# design.net
KiCad netlist of a schematic drawn in EasyEDA Pro
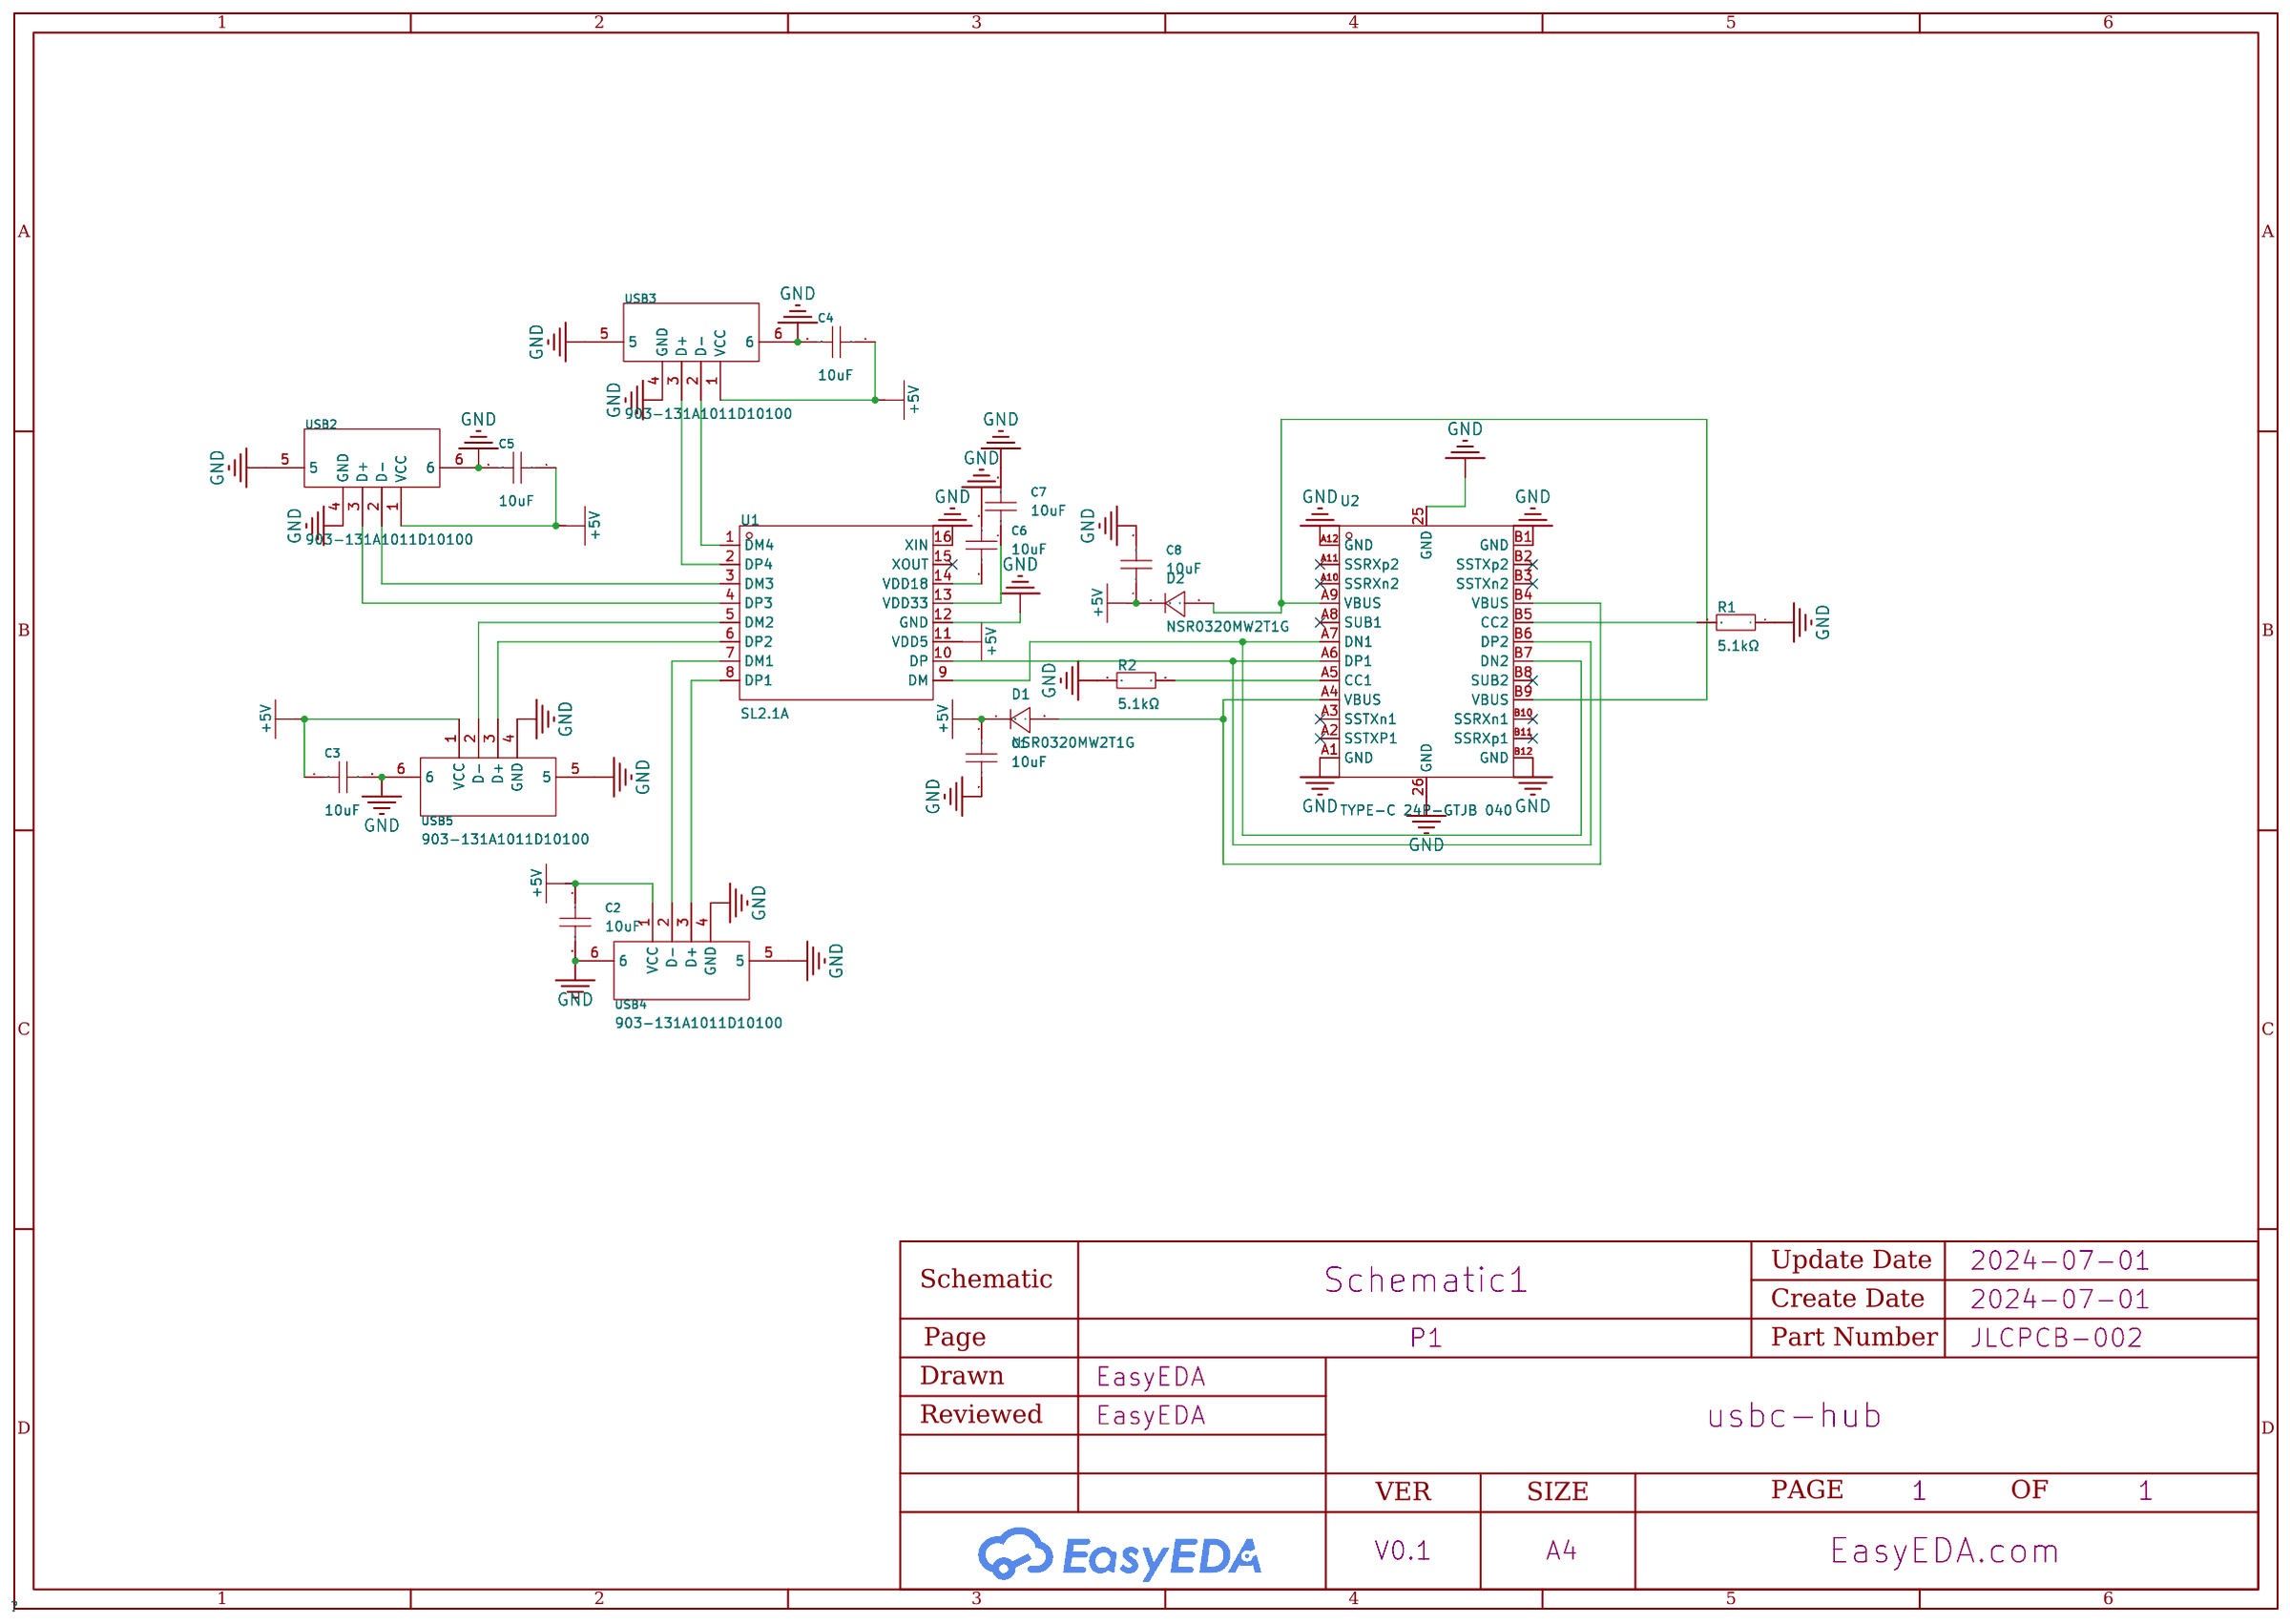
[diagram p0: schematic sheet]

(export (version "E")
  (design (tool "Eeschema 10.0.6"))
  (components
    (comp (ref "C1")
      (value "10uF")
      (footprint "easyedapro:C0603")
      (fields
        (field (name "Manufacturer Part") "CL10A106KP8NNNC")
        (field (name "Manufacturer") "SAMSUNG(三星)")
      )
      (libsource (lib "easyedapro") (part "CL10A106KP8NNNC"))
    )
    (comp (ref "C2")
      (value "10uF")
      (footprint "easyedapro:C0603")
      (fields
        (field (name "Manufacturer Part") "CL10A106KP8NNNC")
        (field (name "Manufacturer") "SAMSUNG(三星)")
      )
      (libsource (lib "easyedapro") (part "CL10A106KP8NNNC"))
    )
    (comp (ref "C3")
      (value "10uF")
      (footprint "easyedapro:C0603")
      (fields
        (field (name "Manufacturer Part") "CL10A106KP8NNNC")
        (field (name "Manufacturer") "SAMSUNG(三星)")
      )
      (libsource (lib "easyedapro") (part "CL10A106KP8NNNC"))
    )
    (comp (ref "C4")
      (value "10uF")
      (footprint "easyedapro:C0603")
      (fields
        (field (name "Manufacturer Part") "CL10A106KP8NNNC")
        (field (name "Manufacturer") "SAMSUNG(三星)")
      )
      (libsource (lib "easyedapro") (part "CL10A106KP8NNNC"))
    )
    (comp (ref "C5")
      (value "10uF")
      (footprint "easyedapro:C0603")
      (fields
        (field (name "Manufacturer Part") "CL10A106KP8NNNC")
        (field (name "Manufacturer") "SAMSUNG(三星)")
      )
      (libsource (lib "easyedapro") (part "CL10A106KP8NNNC"))
    )
    (comp (ref "C6")
      (value "10uF")
      (footprint "easyedapro:C0603")
      (fields
        (field (name "Manufacturer Part") "CL10A106KP8NNNC")
        (field (name "Manufacturer") "SAMSUNG(三星)")
      )
      (libsource (lib "easyedapro") (part "CL10A106KP8NNNC"))
    )
    (comp (ref "C7")
      (value "10uF")
      (footprint "easyedapro:C0603")
      (fields
        (field (name "Manufacturer Part") "CL10A106KP8NNNC")
        (field (name "Manufacturer") "SAMSUNG(三星)")
      )
      (libsource (lib "easyedapro") (part "CL10A106KP8NNNC"))
    )
    (comp (ref "C8")
      (value "10uF")
      (footprint "easyedapro:C0603")
      (fields
        (field (name "Manufacturer Part") "CL10A106KP8NNNC")
        (field (name "Manufacturer") "SAMSUNG(三星)")
      )
      (libsource (lib "easyedapro") (part "CL10A106KP8NNNC"))
    )
    (comp (ref "D1")
      (value "NSR0320MW2T1G")
      (footprint "easyedapro:SOD-323_L1.8-W1.3-LS2.5-RD")
      (fields (field (name "Manufacturer") "onsemi(安森美)"))
      (libsource (lib "easyedapro") (part "NSR0320MW2T1G"))
    )
    (comp (ref "D2")
      (value "NSR0320MW2T1G")
      (footprint "easyedapro:SOD-323_L1.8-W1.3-LS2.5-RD")
      (fields (field (name "Manufacturer") "onsemi(安森美)"))
      (libsource (lib "easyedapro") (part "NSR0320MW2T1G"))
    )
    (comp (ref "R1")
      (value "5.1kΩ")
      (footprint "easyedapro:R0603")
      (libsource (lib "easyedapro") (part "Res"))
    )
    (comp (ref "R2")
      (value "5.1kΩ")
      (footprint "easyedapro:R0603")
      (libsource (lib "easyedapro") (part "Res"))
    )
    (comp (ref "U1")
      (value "SL2.1A")
      (footprint "easyedapro:SOP-16_L10.0-W3.9-P1.27-LS6.0-BL")
      (fields (field (name "Manufacturer") "CoreChips(和芯润德)"))
      (libsource (lib "easyedapro") (part "SL2.1A"))
    )
    (comp (ref "U2")
      (value "TYPE-C 24P-GTJB 040")
      (footprint "easyedapro:USB-C-SMD_TYPE-C-24P-GTJB-040")
      (fields (field (name "Manufacturer") "SHOU HAN(首韩)"))
      (libsource (lib "easyedapro") (part "TYPE-C 24P-GTJB 040"))
    )
    (comp (ref "USB2")
      (value "903-131A1011D10100")
      (footprint "easyedapro:USB-A-TH_C46407")
      (fields (field (name "Manufacturer") "精拓金"))
      (libsource (lib "easyedapro") (part "USB-AF-90-14.4X13.6-H7.0-DIP"))
    )
    (comp (ref "USB3")
      (value "903-131A1011D10100")
      (footprint "easyedapro:USB-A-TH_C46407")
      (fields (field (name "Manufacturer") "精拓金"))
      (libsource (lib "easyedapro") (part "USB-AF-90-14.4X13.6-H7.0-DIP"))
    )
    (comp (ref "USB4")
      (value "903-131A1011D10100")
      (footprint "easyedapro:USB-A-TH_C46407")
      (fields (field (name "Manufacturer") "精拓金"))
      (libsource (lib "easyedapro") (part "USB-AF-90-14.4X13.6-H7.0-DIP"))
    )
    (comp (ref "USB5")
      (value "903-131A1011D10100")
      (footprint "easyedapro:USB-A-TH_C46407")
      (fields (field (name "Manufacturer") "精拓金"))
      (libsource (lib "easyedapro") (part "USB-AF-90-14.4X13.6-H7.0-DIP"))
    )
  )
  (nets
    (net (code "1") (name "+5V") (class "Default")
      (node (ref "C1") (pin "1") (pinfunction "1_1") (pintype "input"))
      (node (ref "C2") (pin "1") (pinfunction "1_1") (pintype "input"))
      (node (ref "C3") (pin "1") (pinfunction "1_1") (pintype "input"))
      (node (ref "C4") (pin "1") (pinfunction "1_1") (pintype "input"))
      (node (ref "C5") (pin "1") (pinfunction "1_1") (pintype "input"))
      (node (ref "C8") (pin "1") (pinfunction "1_1") (pintype "input"))
      (node (ref "D1") (pin "1") (pinfunction "C_1") (pintype "unspecified"))
      (node (ref "D2") (pin "1") (pinfunction "C_1") (pintype "unspecified"))
      (node (ref "U1") (pin "11") (pinfunction "VDD5_11") (pintype "unspecified"))
      (node (ref "USB2") (pin "1") (pinfunction "VCC_1") (pintype "input"))
      (node (ref "USB3") (pin "1") (pinfunction "VCC_1") (pintype "input"))
      (node (ref "USB4") (pin "1") (pinfunction "VCC_1") (pintype "input"))
      (node (ref "USB5") (pin "1") (pinfunction "VCC_1") (pintype "input"))
    )
    (net (code "2") (name "GND") (class "Default")
      (node (ref "C1") (pin "2") (pinfunction "2_2") (pintype "input"))
      (node (ref "C2") (pin "2") (pinfunction "2_2") (pintype "input"))
      (node (ref "C3") (pin "2") (pinfunction "2_2") (pintype "input"))
      (node (ref "C4") (pin "2") (pinfunction "2_2") (pintype "input"))
      (node (ref "C5") (pin "2") (pinfunction "2_2") (pintype "input"))
      (node (ref "C6") (pin "2") (pinfunction "2_2") (pintype "input"))
      (node (ref "C7") (pin "2") (pinfunction "2_2") (pintype "input"))
      (node (ref "C8") (pin "2") (pinfunction "2_2") (pintype "input"))
      (node (ref "R1") (pin "1") (pinfunction "1_1") (pintype "input"))
      (node (ref "R2") (pin "1") (pinfunction "1_1") (pintype "input"))
      (node (ref "U1") (pin "12") (pinfunction "GND_12") (pintype "unspecified"))
      (node (ref "U1") (pin "16") (pinfunction "XIN_16") (pintype "unspecified"))
      (node (ref "U2") (pin "25") (pinfunction "GND_25") (pintype "unspecified"))
      (node (ref "U2") (pin "26") (pinfunction "GND_26") (pintype "unspecified"))
      (node (ref "U2") (pin "A1") (pinfunction "GND_A1") (pintype "unspecified"))
      (node (ref "U2") (pin "A12") (pinfunction "GND_A12") (pintype "unspecified"))
      (node (ref "U2") (pin "B1") (pinfunction "GND_B1") (pintype "unspecified"))
      (node (ref "U2") (pin "B12") (pinfunction "GND_B12") (pintype "unspecified"))
      (node (ref "USB2") (pin "4") (pinfunction "GND_4") (pintype "input"))
      (node (ref "USB2") (pin "5") (pinfunction "5_5") (pintype "input"))
      (node (ref "USB2") (pin "6") (pinfunction "6_6") (pintype "input"))
      (node (ref "USB3") (pin "4") (pinfunction "GND_4") (pintype "input"))
      (node (ref "USB3") (pin "5") (pinfunction "5_5") (pintype "input"))
      (node (ref "USB3") (pin "6") (pinfunction "6_6") (pintype "input"))
      (node (ref "USB4") (pin "4") (pinfunction "GND_4") (pintype "input"))
      (node (ref "USB4") (pin "5") (pinfunction "5_5") (pintype "input"))
      (node (ref "USB4") (pin "6") (pinfunction "6_6") (pintype "input"))
      (node (ref "USB5") (pin "4") (pinfunction "GND_4") (pintype "input"))
      (node (ref "USB5") (pin "5") (pinfunction "5_5") (pintype "input"))
      (node (ref "USB5") (pin "6") (pinfunction "6_6") (pintype "input"))
    )
    (net (code "3") (name "Net-(D1-A)") (class "Default")
      (node (ref "D1") (pin "2") (pinfunction "A_2") (pintype "unspecified"))
      (node (ref "U2") (pin "A4") (pinfunction "VBUS_A4") (pintype "unspecified"))
      (node (ref "U2") (pin "B4") (pinfunction "VBUS_B4") (pintype "unspecified"))
    )
    (net (code "4") (name "Net-(D2-A)") (class "Default")
      (node (ref "D2") (pin "2") (pinfunction "A_2") (pintype "unspecified"))
      (node (ref "U2") (pin "A9") (pinfunction "VBUS_A9") (pintype "unspecified"))
      (node (ref "U2") (pin "B9") (pinfunction "VBUS_B9") (pintype "unspecified"))
    )
    (net (code "5") (name "Net-(U1-DM)") (class "Default")
      (node (ref "U1") (pin "9") (pinfunction "DM_9") (pintype "unspecified"))
      (node (ref "U2") (pin "A7") (pinfunction "DN1_A7") (pintype "unspecified"))
      (node (ref "U2") (pin "B7") (pinfunction "DN2_B7") (pintype "unspecified"))
    )
    (net (code "6") (name "Net-(U1-DM1)") (class "Default")
      (node (ref "U1") (pin "7") (pinfunction "DM1_7") (pintype "unspecified"))
      (node (ref "USB4") (pin "2") (pinfunction "D-_2") (pintype "input"))
    )
    (net (code "7") (name "Net-(U1-DM2)") (class "Default")
      (node (ref "U1") (pin "5") (pinfunction "DM2_5") (pintype "unspecified"))
      (node (ref "USB5") (pin "2") (pinfunction "D-_2") (pintype "input"))
    )
    (net (code "8") (name "Net-(U1-DM3)") (class "Default")
      (node (ref "U1") (pin "3") (pinfunction "DM3_3") (pintype "unspecified"))
      (node (ref "USB2") (pin "2") (pinfunction "D-_2") (pintype "input"))
    )
    (net (code "9") (name "Net-(U1-DM4)") (class "Default")
      (node (ref "U1") (pin "1") (pinfunction "DM4_1") (pintype "unspecified"))
      (node (ref "USB3") (pin "2") (pinfunction "D-_2") (pintype "input"))
    )
    (net (code "10") (name "Net-(U1-DP)") (class "Default")
      (node (ref "U1") (pin "10") (pinfunction "DP_10") (pintype "unspecified"))
      (node (ref "U2") (pin "A6") (pinfunction "DP1_A6") (pintype "unspecified"))
      (node (ref "U2") (pin "B6") (pinfunction "DP2_B6") (pintype "unspecified"))
    )
    (net (code "11") (name "Net-(U1-DP1)") (class "Default")
      (node (ref "U1") (pin "8") (pinfunction "DP1_8") (pintype "unspecified"))
      (node (ref "USB4") (pin "3") (pinfunction "D+_3") (pintype "input"))
    )
    (net (code "12") (name "Net-(U1-DP2)") (class "Default")
      (node (ref "U1") (pin "6") (pinfunction "DP2_6") (pintype "unspecified"))
      (node (ref "USB5") (pin "3") (pinfunction "D+_3") (pintype "input"))
    )
    (net (code "13") (name "Net-(U1-DP3)") (class "Default")
      (node (ref "U1") (pin "4") (pinfunction "DP3_4") (pintype "unspecified"))
      (node (ref "USB2") (pin "3") (pinfunction "D+_3") (pintype "input"))
    )
    (net (code "14") (name "Net-(U1-DP4)") (class "Default")
      (node (ref "U1") (pin "2") (pinfunction "DP4_2") (pintype "unspecified"))
      (node (ref "USB3") (pin "3") (pinfunction "D+_3") (pintype "input"))
    )
    (net (code "15") (name "Net-(U1-VDD18)") (class "Default")
      (node (ref "C6") (pin "1") (pinfunction "1_1") (pintype "input"))
      (node (ref "U1") (pin "14") (pinfunction "VDD18_14") (pintype "unspecified"))
    )
    (net (code "16") (name "Net-(U1-VDD33)") (class "Default")
      (node (ref "C7") (pin "1") (pinfunction "1_1") (pintype "input"))
      (node (ref "U1") (pin "13") (pinfunction "VDD33_13") (pintype "unspecified"))
    )
    (net (code "17") (name "Net-(U2-CC1)") (class "Default")
      (node (ref "R2") (pin "2") (pinfunction "2_2") (pintype "input"))
      (node (ref "U2") (pin "A5") (pinfunction "CC1_A5") (pintype "unspecified"))
    )
    (net (code "18") (name "Net-(U2-CC2)") (class "Default")
      (node (ref "R1") (pin "2") (pinfunction "2_2") (pintype "input"))
      (node (ref "U2") (pin "B5") (pinfunction "CC2_B5") (pintype "unspecified"))
    )
    (net (code "19") (name "unconnected-(U1-XOUT-Pad15)") (class "Default")
      (node (ref "U1") (pin "15") (pinfunction "XOUT_15") (pintype "unspecified+no_connect"))
    )
    (net (code "20") (name "unconnected-(U2-SSRXn1-PadB10)") (class "Default")
      (node (ref "U2") (pin "B10") (pinfunction "SSRXn1_B10") (pintype "unspecified+no_connect"))
    )
    (net (code "21") (name "unconnected-(U2-SSRXn2-PadA10)") (class "Default")
      (node (ref "U2") (pin "A10") (pinfunction "SSRXn2_A10") (pintype "unspecified+no_connect"))
    )
    (net (code "22") (name "unconnected-(U2-SSRXp1-PadB11)") (class "Default")
      (node (ref "U2") (pin "B11") (pinfunction "SSRXp1_B11") (pintype "unspecified+no_connect"))
    )
    (net (code "23") (name "unconnected-(U2-SSRXp2-PadA11)") (class "Default")
      (node (ref "U2") (pin "A11") (pinfunction "SSRXp2_A11") (pintype "unspecified+no_connect"))
    )
    (net (code "24") (name "unconnected-(U2-SSTXP1-PadA2)") (class "Default")
      (node (ref "U2") (pin "A2") (pinfunction "SSTXP1_A2") (pintype "unspecified+no_connect"))
    )
    (net (code "25") (name "unconnected-(U2-SSTXn1-PadA3)") (class "Default")
      (node (ref "U2") (pin "A3") (pinfunction "SSTXn1_A3") (pintype "unspecified+no_connect"))
    )
    (net (code "26") (name "unconnected-(U2-SSTXn2-PadB3)") (class "Default")
      (node (ref "U2") (pin "B3") (pinfunction "SSTXn2_B3") (pintype "unspecified+no_connect"))
    )
    (net (code "27") (name "unconnected-(U2-SSTXp2-PadB2)") (class "Default")
      (node (ref "U2") (pin "B2") (pinfunction "SSTXp2_B2") (pintype "unspecified+no_connect"))
    )
    (net (code "28") (name "unconnected-(U2-SUB1-PadA8)") (class "Default")
      (node (ref "U2") (pin "A8") (pinfunction "SUB1_A8") (pintype "unspecified+no_connect"))
    )
    (net (code "29") (name "unconnected-(U2-SUB2-PadB8)") (class "Default")
      (node (ref "U2") (pin "B8") (pinfunction "SUB2_B8") (pintype "unspecified+no_connect"))
    )
  )
)
